# SFP.net
KiCad netlist of a schematic drawn in Altium Designer
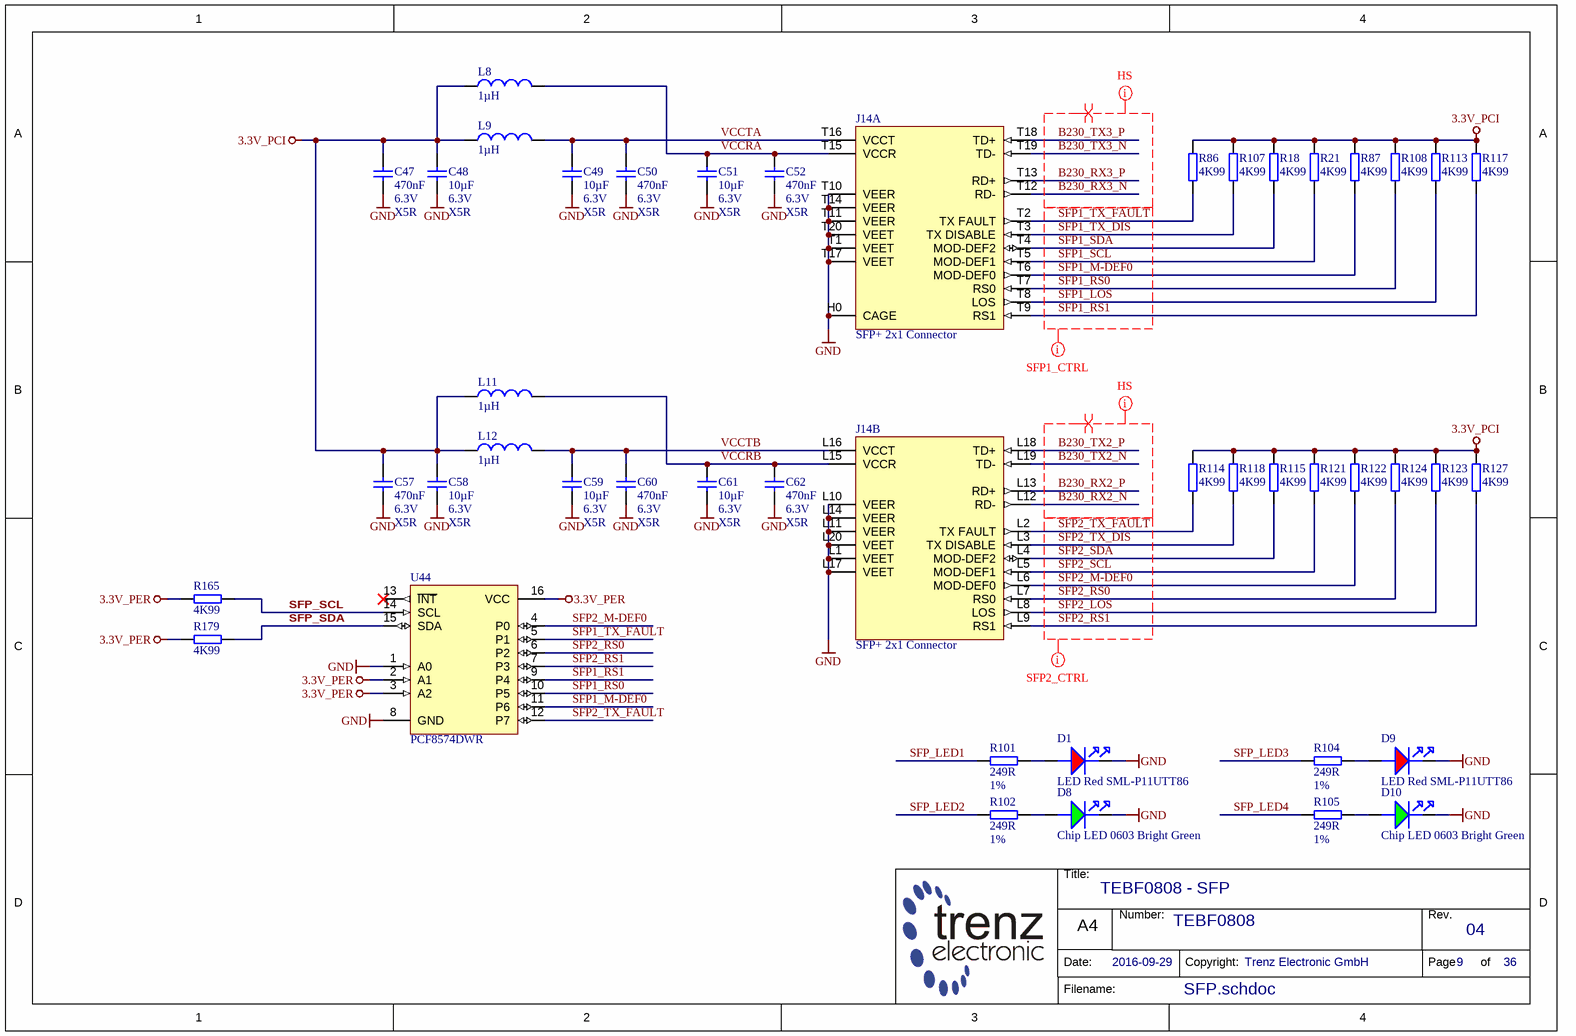
[diagram p0: SFP.schdoc]

(export (version "E")
  (design (tool "Eeschema 10.0.6"))
  (components
    (comp (ref "C47")
      (value "470nF")
      (footprint "CAPC1005X55N")
      (description "KON 470nF 6,3V X5R SMD")
      (fields (field (name "VOLTAGE") "6.3V") (field (name "TECHNOLOGY") "X5R"))
      (libsource (lib "TE") (part "CAP-NP"))
    )
    (comp (ref "C48")
      (value "10µF")
      (footprint "CAPC1608X90N")
      (description "KON 10µF 6,3V X5R SMD")
      (fields (field (name "VOLTAGE") "6.3V") (field (name "TECHNOLOGY") "X5R"))
      (libsource (lib "TE") (part "CAP-NP"))
    )
    (comp (ref "C49")
      (value "10µF")
      (footprint "CAPC1608X90N")
      (description "KON 10µF 6,3V X5R SMD")
      (fields (field (name "VOLTAGE") "6.3V") (field (name "TECHNOLOGY") "X5R"))
      (libsource (lib "TE") (part "CAP-NP"))
    )
    (comp (ref "C50")
      (value "470nF")
      (footprint "CAPC1005X55N")
      (description "KON 470nF 6,3V X5R SMD")
      (fields (field (name "VOLTAGE") "6.3V") (field (name "TECHNOLOGY") "X5R"))
      (libsource (lib "TE") (part "CAP-NP"))
    )
    (comp (ref "C51")
      (value "10µF")
      (footprint "CAPC1608X90N")
      (description "KON 10µF 6,3V X5R SMD")
      (fields (field (name "VOLTAGE") "6.3V") (field (name "TECHNOLOGY") "X5R"))
      (libsource (lib "TE") (part "CAP-NP"))
    )
    (comp (ref "C52")
      (value "470nF")
      (footprint "CAPC1005X55N")
      (description "KON 470nF 6,3V X5R SMD")
      (fields (field (name "VOLTAGE") "6.3V") (field (name "TECHNOLOGY") "X5R"))
      (libsource (lib "TE") (part "CAP-NP"))
    )
    (comp (ref "C57")
      (value "470nF")
      (footprint "CAPC1005X55N")
      (description "KON 470nF 6,3V X5R SMD")
      (fields (field (name "VOLTAGE") "6.3V") (field (name "TECHNOLOGY") "X5R"))
      (libsource (lib "TE") (part "CAP-NP"))
    )
    (comp (ref "C58")
      (value "10µF")
      (footprint "CAPC1608X90N")
      (description "KON 10µF 6,3V X5R SMD")
      (fields (field (name "VOLTAGE") "6.3V") (field (name "TECHNOLOGY") "X5R"))
      (libsource (lib "TE") (part "CAP-NP"))
    )
    (comp (ref "C59")
      (value "10µF")
      (footprint "CAPC1608X90N")
      (description "KON 10µF 6,3V X5R SMD")
      (fields (field (name "VOLTAGE") "6.3V") (field (name "TECHNOLOGY") "X5R"))
      (libsource (lib "TE") (part "CAP-NP"))
    )
    (comp (ref "C60")
      (value "470nF")
      (footprint "CAPC1005X55N")
      (description "KON 470nF 6,3V X5R SMD")
      (fields (field (name "VOLTAGE") "6.3V") (field (name "TECHNOLOGY") "X5R"))
      (libsource (lib "TE") (part "CAP-NP"))
    )
    (comp (ref "C61")
      (value "10µF")
      (footprint "CAPC1608X90N")
      (description "KON 10µF 6,3V X5R SMD")
      (fields (field (name "VOLTAGE") "6.3V") (field (name "TECHNOLOGY") "X5R"))
      (libsource (lib "TE") (part "CAP-NP"))
    )
    (comp (ref "C62")
      (value "470nF")
      (footprint "CAPC1005X55N")
      (description "KON 470nF 6,3V X5R SMD")
      (fields (field (name "VOLTAGE") "6.3V") (field (name "TECHNOLOGY") "X5R"))
      (libsource (lib "TE") (part "CAP-NP"))
    )
    (comp (ref "D1")
      (value "LED Red SML-P11UTT86")
      (footprint "LEDC1006X25N_RED")
      (description "LED Rot SML-P11UTT86 SMD")
      (libsource (lib "TE") (part "LED_ROT"))
    )
    (comp (ref "D8")
      (value "Chip LED 0603 Bright Green")
      (footprint "chipLED_0603_Green")
      (fields (field (name "VOLTAGE") "2.0"))
      (libsource (lib "TE") (part "LED_GRUEN"))
    )
    (comp (ref "D9")
      (value "LED Red SML-P11UTT86")
      (footprint "LEDC1006X25N_RED")
      (description "LED Rot SML-P11UTT86 SMD")
      (libsource (lib "TE") (part "LED_ROT"))
    )
    (comp (ref "D10")
      (value "Chip LED 0603 Bright Green")
      (footprint "chipLED_0603_Green")
      (fields (field (name "VOLTAGE") "2.0"))
      (libsource (lib "TE") (part "LED_GRUEN"))
    )
    (comp (ref "J14")
      (value "SFP+ 2x1 Connector")
      (footprint "1-2007492-5")
      (description "SFP+ 2x1 Connector  Sp Fing 4LP EMI Enhanced")
      (libsource (lib "TE") (part "1-2007492-5"))
    )
    (comp (ref "L8")
      (value "1µH")
      (footprint "INDC2520X100N")
      (description "IND SMD 1µH +-20% 0.055Ohm")
      (fields (field (name "VOLTAGE") "1.7A"))
      (libsource (lib "TE") (part "IND"))
    )
    (comp (ref "L9")
      (value "1µH")
      (footprint "INDC2520X100N")
      (description "IND SMD 1µH +-20% 0.055Ohm")
      (fields (field (name "VOLTAGE") "1.7A"))
      (libsource (lib "TE") (part "IND"))
    )
    (comp (ref "L11")
      (value "1µH")
      (footprint "INDC2520X100N")
      (description "IND SMD 1µH +-20% 0.055Ohm")
      (fields (field (name "VOLTAGE") "1.7A"))
      (libsource (lib "TE") (part "IND"))
    )
    (comp (ref "L12")
      (value "1µH")
      (footprint "INDC2520X100N")
      (description "IND SMD 1µH +-20% 0.055Ohm")
      (fields (field (name "VOLTAGE") "1.7A"))
      (libsource (lib "TE") (part "IND"))
    )
    (comp (ref "R18")
      (value "4K99")
      (footprint "RESC1005X40N")
      (description "WID SMD 4K99 1% 0,063W")
      (fields (field (name "TOLERANCE") "1%"))
      (libsource (lib "TE") (part "RES"))
    )
    (comp (ref "R21")
      (value "4K99")
      (footprint "RESC1005X40N")
      (description "WID SMD 4K99 1% 0,063W")
      (fields (field (name "TOLERANCE") "1%"))
      (libsource (lib "TE") (part "RES"))
    )
    (comp (ref "R86")
      (value "4K99")
      (footprint "RESC1005X40N")
      (description "WID SMD 4K99 1% 0,063W")
      (fields (field (name "TOLERANCE") "1%"))
      (libsource (lib "TE") (part "RES"))
    )
    (comp (ref "R87")
      (value "4K99")
      (footprint "RESC1005X40N")
      (description "WID SMD 4K99 1% 0,063W")
      (fields (field (name "TOLERANCE") "1%"))
      (libsource (lib "TE") (part "RES"))
    )
    (comp (ref "R101")
      (value "249R")
      (footprint "RESC1005X40N")
      (description "WID SMD 249R 1% 0,063W")
      (fields (field (name "TOLERANCE") "1%"))
      (libsource (lib "TE") (part "RES"))
    )
    (comp (ref "R102")
      (value "249R")
      (footprint "RESC1005X40N")
      (description "WID SMD 249R 1% 0,063W")
      (fields (field (name "TOLERANCE") "1%"))
      (libsource (lib "TE") (part "RES"))
    )
    (comp (ref "R104")
      (value "249R")
      (footprint "RESC1005X40N")
      (description "WID SMD 249R 1% 0,063W")
      (fields (field (name "TOLERANCE") "1%"))
      (libsource (lib "TE") (part "RES"))
    )
    (comp (ref "R105")
      (value "249R")
      (footprint "RESC1005X40N")
      (description "WID SMD 249R 1% 0,063W")
      (fields (field (name "TOLERANCE") "1%"))
      (libsource (lib "TE") (part "RES"))
    )
    (comp (ref "R107")
      (value "4K99")
      (footprint "RESC1005X40N")
      (description "WID SMD 4K99 1% 0,063W")
      (fields (field (name "TOLERANCE") "1%"))
      (libsource (lib "TE") (part "RES"))
    )
    (comp (ref "R108")
      (value "4K99")
      (footprint "RESC1005X40N")
      (description "WID SMD 4K99 1% 0,063W")
      (fields (field (name "TOLERANCE") "1%"))
      (libsource (lib "TE") (part "RES"))
    )
    (comp (ref "R113")
      (value "4K99")
      (footprint "RESC1005X40N")
      (description "WID SMD 4K99 1% 0,063W")
      (fields (field (name "TOLERANCE") "1%"))
      (libsource (lib "TE") (part "RES"))
    )
    (comp (ref "R114")
      (value "4K99")
      (footprint "RESC1005X40N")
      (description "WID SMD 4K99 1% 0,063W")
      (fields (field (name "TOLERANCE") "1%"))
      (libsource (lib "TE") (part "RES"))
    )
    (comp (ref "R115")
      (value "4K99")
      (footprint "RESC1005X40N")
      (description "WID SMD 4K99 1% 0,063W")
      (fields (field (name "TOLERANCE") "1%"))
      (libsource (lib "TE") (part "RES"))
    )
    (comp (ref "R117")
      (value "4K99")
      (footprint "RESC1005X40N")
      (description "WID SMD 4K99 1% 0,063W")
      (fields (field (name "TOLERANCE") "1%"))
      (libsource (lib "TE") (part "RES"))
    )
    (comp (ref "R118")
      (value "4K99")
      (footprint "RESC1005X40N")
      (description "WID SMD 4K99 1% 0,063W")
      (fields (field (name "TOLERANCE") "1%"))
      (libsource (lib "TE") (part "RES"))
    )
    (comp (ref "R121")
      (value "4K99")
      (footprint "RESC1005X40N")
      (description "WID SMD 4K99 1% 0,063W")
      (fields (field (name "TOLERANCE") "1%"))
      (libsource (lib "TE") (part "RES"))
    )
    (comp (ref "R122")
      (value "4K99")
      (footprint "RESC1005X40N")
      (description "WID SMD 4K99 1% 0,063W")
      (fields (field (name "TOLERANCE") "1%"))
      (libsource (lib "TE") (part "RES"))
    )
    (comp (ref "R123")
      (value "4K99")
      (footprint "RESC1005X40N")
      (description "WID SMD 4K99 1% 0,063W")
      (fields (field (name "TOLERANCE") "1%"))
      (libsource (lib "TE") (part "RES"))
    )
    (comp (ref "R124")
      (value "4K99")
      (footprint "RESC1005X40N")
      (description "WID SMD 4K99 1% 0,063W")
      (fields (field (name "TOLERANCE") "1%"))
      (libsource (lib "TE") (part "RES"))
    )
    (comp (ref "R127")
      (value "4K99")
      (footprint "RESC1005X40N")
      (description "WID SMD 4K99 1% 0,063W")
      (fields (field (name "TOLERANCE") "1%"))
      (libsource (lib "TE") (part "RES"))
    )
    (comp (ref "R165")
      (value "4K99")
      (footprint "RESC1005X40N")
      (description "WID SMD 4K99 1% 0,063W")
      (fields (field (name "TOLERANCE") "1%"))
      (libsource (lib "TE") (part "RES"))
    )
    (comp (ref "R179")
      (value "4K99")
      (footprint "RESC1005X40N")
      (description "WID SMD 4K99 1% 0,063W")
      (fields (field (name "TOLERANCE") "1%"))
      (libsource (lib "TE") (part "RES"))
    )
    (comp (ref "U44")
      (value "PCF8574DWR")
      (footprint "SOIC127P1030X265-16N")
      (libsource (lib "TE") (part "PCF8574DWR"))
    )
  )
  (nets
    (net (code "1") (name "/B230_RX2_N") (class "Default")
      (node (ref "J14") (pin "L12") (pinfunction "RD-_L12") (pintype "output"))
    )
    (net (code "2") (name "/B230_RX2_P") (class "Default")
      (node (ref "J14") (pin "L13") (pinfunction "RD+_L13") (pintype "output"))
    )
    (net (code "3") (name "/B230_RX3_N") (class "Default")
      (node (ref "J14") (pin "T12") (pinfunction "RD-_T12") (pintype "output"))
    )
    (net (code "4") (name "/B230_RX3_P") (class "Default")
      (node (ref "J14") (pin "T13") (pinfunction "RD+_T13") (pintype "output"))
    )
    (net (code "5") (name "/B230_TX2_N") (class "Default")
      (node (ref "J14") (pin "L19") (pinfunction "TD-_L19") (pintype "input"))
    )
    (net (code "6") (name "/B230_TX2_P") (class "Default")
      (node (ref "J14") (pin "L18") (pinfunction "TD+_L18") (pintype "input"))
    )
    (net (code "7") (name "/B230_TX3_N") (class "Default")
      (node (ref "J14") (pin "T19") (pinfunction "TD-_T19") (pintype "input"))
    )
    (net (code "8") (name "/B230_TX3_P") (class "Default")
      (node (ref "J14") (pin "T18") (pinfunction "TD+_T18") (pintype "input"))
    )
    (net (code "9") (name "/SFP1_LOS") (class "Default")
      (node (ref "J14") (pin "T8") (pinfunction "LOS_T8") (pintype "output"))
      (node (ref "R113") (pin "1") (pinfunction "1_1") (pintype "passive"))
    )
    (net (code "10") (name "/SFP1_M-DEF0") (class "Default")
      (node (ref "J14") (pin "T6") (pinfunction "MOD-DEF0_T6") (pintype "output"))
      (node (ref "R87") (pin "1") (pinfunction "1_1") (pintype "passive"))
      (node (ref "U44") (pin "11") (pinfunction "P6_11") (pintype "bidirectional"))
    )
    (net (code "11") (name "/SFP1_RS0") (class "Default")
      (node (ref "J14") (pin "T7") (pinfunction "RS0_T7") (pintype "input"))
      (node (ref "R108") (pin "1") (pinfunction "1_1") (pintype "passive"))
      (node (ref "U44") (pin "10") (pinfunction "P5_10") (pintype "bidirectional"))
    )
    (net (code "12") (name "/SFP1_RS1") (class "Default")
      (node (ref "J14") (pin "T9") (pinfunction "RS1_T9") (pintype "input"))
      (node (ref "R117") (pin "1") (pinfunction "1_1") (pintype "passive"))
      (node (ref "U44") (pin "9") (pinfunction "P4_9") (pintype "bidirectional"))
    )
    (net (code "13") (name "/SFP1_SCL") (class "Default")
      (node (ref "J14") (pin "T5") (pinfunction "MOD-DEF1_T5") (pintype "input"))
      (node (ref "R21") (pin "1") (pinfunction "1_1") (pintype "passive"))
    )
    (net (code "14") (name "/SFP1_SDA") (class "Default")
      (node (ref "J14") (pin "T4") (pinfunction "MOD-DEF2_T4") (pintype "bidirectional"))
      (node (ref "R18") (pin "1") (pinfunction "1_1") (pintype "passive"))
    )
    (net (code "15") (name "/SFP1_TX_DIS") (class "Default")
      (node (ref "J14") (pin "T3") (pinfunction "TX_DISABLE_T3") (pintype "input"))
      (node (ref "R107") (pin "1") (pinfunction "1_1") (pintype "passive"))
    )
    (net (code "16") (name "/SFP1_TX_FAULT") (class "Default")
      (node (ref "J14") (pin "T2") (pinfunction "TX_FAULT_T2") (pintype "output"))
      (node (ref "R86") (pin "1") (pinfunction "1_1") (pintype "passive"))
      (node (ref "U44") (pin "5") (pinfunction "P1_5") (pintype "bidirectional"))
    )
    (net (code "17") (name "/SFP2_LOS") (class "Default")
      (node (ref "J14") (pin "L8") (pinfunction "LOS_L8") (pintype "output"))
      (node (ref "R123") (pin "1") (pinfunction "1_1") (pintype "passive"))
    )
    (net (code "18") (name "/SFP2_M-DEF0") (class "Default")
      (node (ref "J14") (pin "L6") (pinfunction "MOD-DEF0_L6") (pintype "output"))
      (node (ref "R122") (pin "1") (pinfunction "1_1") (pintype "passive"))
      (node (ref "U44") (pin "4") (pinfunction "P0_4") (pintype "bidirectional"))
    )
    (net (code "19") (name "/SFP2_RS0") (class "Default")
      (node (ref "J14") (pin "L7") (pinfunction "RS0_L7") (pintype "input"))
      (node (ref "R124") (pin "1") (pinfunction "1_1") (pintype "passive"))
      (node (ref "U44") (pin "6") (pinfunction "P2_6") (pintype "bidirectional"))
    )
    (net (code "20") (name "/SFP2_RS1") (class "Default")
      (node (ref "J14") (pin "L9") (pinfunction "RS1_L9") (pintype "input"))
      (node (ref "R127") (pin "1") (pinfunction "1_1") (pintype "passive"))
      (node (ref "U44") (pin "7") (pinfunction "P3_7") (pintype "bidirectional"))
    )
    (net (code "21") (name "/SFP2_SCL") (class "Default")
      (node (ref "J14") (pin "L5") (pinfunction "MOD-DEF1_L5") (pintype "input"))
      (node (ref "R121") (pin "1") (pinfunction "1_1") (pintype "passive"))
    )
    (net (code "22") (name "/SFP2_SDA") (class "Default")
      (node (ref "J14") (pin "L4") (pinfunction "MOD-DEF2_L4") (pintype "bidirectional"))
      (node (ref "R115") (pin "1") (pinfunction "1_1") (pintype "passive"))
    )
    (net (code "23") (name "/SFP2_TX_DIS") (class "Default")
      (node (ref "J14") (pin "L3") (pinfunction "TX_DISABLE_L3") (pintype "input"))
      (node (ref "R118") (pin "1") (pinfunction "1_1") (pintype "passive"))
    )
    (net (code "24") (name "/SFP2_TX_FAULT") (class "Default")
      (node (ref "J14") (pin "L2") (pinfunction "TX_FAULT_L2") (pintype "output"))
      (node (ref "R114") (pin "1") (pinfunction "1_1") (pintype "passive"))
      (node (ref "U44") (pin "12") (pinfunction "P7_12") (pintype "bidirectional"))
    )
    (net (code "25") (name "/SFP_LED1") (class "Default")
      (node (ref "R101") (pin "1") (pinfunction "1_1") (pintype "passive"))
    )
    (net (code "26") (name "/SFP_LED2") (class "Default")
      (node (ref "R102") (pin "1") (pinfunction "1_1") (pintype "passive"))
    )
    (net (code "27") (name "/SFP_LED3") (class "Default")
      (node (ref "R104") (pin "1") (pinfunction "1_1") (pintype "passive"))
    )
    (net (code "28") (name "/SFP_LED4") (class "Default")
      (node (ref "R105") (pin "1") (pinfunction "1_1") (pintype "passive"))
    )
    (net (code "29") (name "/SFP_SCL") (class "Default")
      (node (ref "R165") (pin "2") (pinfunction "2_2") (pintype "passive"))
      (node (ref "U44") (pin "14") (pinfunction "SCL_14") (pintype "input"))
    )
    (net (code "30") (name "/SFP_SDA") (class "Default")
      (node (ref "R179") (pin "2") (pinfunction "2_2") (pintype "passive"))
      (node (ref "U44") (pin "15") (pinfunction "SDA_15") (pintype "bidirectional"))
    )
    (net (code "31") (name "/VCCRA") (class "Default")
      (node (ref "C51") (pin "1") (pinfunction "1_1") (pintype "passive"))
      (node (ref "C52") (pin "1") (pinfunction "1_1") (pintype "passive"))
      (node (ref "J14") (pin "T15") (pinfunction "VCCR_T15") (pintype "power_in"))
      (node (ref "L8") (pin "2") (pinfunction "2_2") (pintype "passive"))
    )
    (net (code "32") (name "/VCCRB") (class "Default")
      (node (ref "C61") (pin "1") (pinfunction "1_1") (pintype "passive"))
      (node (ref "C62") (pin "1") (pinfunction "1_1") (pintype "passive"))
      (node (ref "J14") (pin "L15") (pinfunction "VCCR_L15") (pintype "power_in"))
      (node (ref "L11") (pin "2") (pinfunction "2_2") (pintype "passive"))
    )
    (net (code "33") (name "/VCCTA") (class "Default")
      (node (ref "C49") (pin "1") (pinfunction "1_1") (pintype "passive"))
      (node (ref "C50") (pin "1") (pinfunction "1_1") (pintype "passive"))
      (node (ref "J14") (pin "T16") (pinfunction "VCCT_T16") (pintype "power_in"))
      (node (ref "L9") (pin "2") (pinfunction "2_2") (pintype "passive"))
    )
    (net (code "34") (name "/VCCTB") (class "Default")
      (node (ref "C59") (pin "1") (pinfunction "1_1") (pintype "passive"))
      (node (ref "C60") (pin "1") (pinfunction "1_1") (pintype "passive"))
      (node (ref "J14") (pin "L16") (pinfunction "VCCT_L16") (pintype "power_in"))
      (node (ref "L12") (pin "2") (pinfunction "2_2") (pintype "passive"))
    )
    (net (code "35") (name "3.3V_PCI") (class "Default")
      (node (ref "C47") (pin "1") (pinfunction "1_1") (pintype "passive"))
      (node (ref "C48") (pin "1") (pinfunction "1_1") (pintype "passive"))
      (node (ref "C57") (pin "1") (pinfunction "1_1") (pintype "passive"))
      (node (ref "C58") (pin "1") (pinfunction "1_1") (pintype "passive"))
      (node (ref "L11") (pin "1") (pinfunction "1_1") (pintype "passive"))
      (node (ref "L12") (pin "1") (pinfunction "1_1") (pintype "passive"))
      (node (ref "L8") (pin "1") (pinfunction "1_1") (pintype "passive"))
      (node (ref "L9") (pin "1") (pinfunction "1_1") (pintype "passive"))
      (node (ref "R107") (pin "2") (pinfunction "2_2") (pintype "passive"))
      (node (ref "R108") (pin "2") (pinfunction "2_2") (pintype "passive"))
      (node (ref "R113") (pin "2") (pinfunction "2_2") (pintype "passive"))
      (node (ref "R114") (pin "2") (pinfunction "2_2") (pintype "passive"))
      (node (ref "R115") (pin "2") (pinfunction "2_2") (pintype "passive"))
      (node (ref "R117") (pin "2") (pinfunction "2_2") (pintype "passive"))
      (node (ref "R118") (pin "2") (pinfunction "2_2") (pintype "passive"))
      (node (ref "R121") (pin "2") (pinfunction "2_2") (pintype "passive"))
      (node (ref "R122") (pin "2") (pinfunction "2_2") (pintype "passive"))
      (node (ref "R123") (pin "2") (pinfunction "2_2") (pintype "passive"))
      (node (ref "R124") (pin "2") (pinfunction "2_2") (pintype "passive"))
      (node (ref "R127") (pin "2") (pinfunction "2_2") (pintype "passive"))
      (node (ref "R18") (pin "2") (pinfunction "2_2") (pintype "passive"))
      (node (ref "R21") (pin "2") (pinfunction "2_2") (pintype "passive"))
      (node (ref "R86") (pin "2") (pinfunction "2_2") (pintype "passive"))
      (node (ref "R87") (pin "2") (pinfunction "2_2") (pintype "passive"))
    )
    (net (code "36") (name "3.3V_PER") (class "Default")
      (node (ref "R165") (pin "1") (pinfunction "1_1") (pintype "passive"))
      (node (ref "R179") (pin "1") (pinfunction "1_1") (pintype "passive"))
      (node (ref "U44") (pin "16") (pinfunction "VCC_16") (pintype "power_in"))
      (node (ref "U44") (pin "2") (pinfunction "A1_2") (pintype "input"))
      (node (ref "U44") (pin "3") (pinfunction "A2_3") (pintype "input"))
    )
    (net (code "37") (name "GND") (class "Default")
      (node (ref "C47") (pin "2") (pinfunction "2_2") (pintype "passive"))
      (node (ref "C48") (pin "2") (pinfunction "2_2") (pintype "passive"))
      (node (ref "C49") (pin "2") (pinfunction "2_2") (pintype "passive"))
      (node (ref "C50") (pin "2") (pinfunction "2_2") (pintype "passive"))
      (node (ref "C51") (pin "2") (pinfunction "2_2") (pintype "passive"))
      (node (ref "C52") (pin "2") (pinfunction "2_2") (pintype "passive"))
      (node (ref "C57") (pin "2") (pinfunction "2_2") (pintype "passive"))
      (node (ref "C58") (pin "2") (pinfunction "2_2") (pintype "passive"))
      (node (ref "C59") (pin "2") (pinfunction "2_2") (pintype "passive"))
      (node (ref "C60") (pin "2") (pinfunction "2_2") (pintype "passive"))
      (node (ref "C61") (pin "2") (pinfunction "2_2") (pintype "passive"))
      (node (ref "C62") (pin "2") (pinfunction "2_2") (pintype "passive"))
      (node (ref "D1") (pin "K") (pinfunction "K_K") (pintype "passive"))
      (node (ref "D10") (pin "K") (pinfunction "K_K") (pintype "passive"))
      (node (ref "D8") (pin "K") (pinfunction "K_K") (pintype "passive"))
      (node (ref "D9") (pin "K") (pinfunction "K_K") (pintype "passive"))
      (node (ref "J14") (pin "H0") (pinfunction "CAGE_H0") (pintype "power_in"))
      (node (ref "J14") (pin "L1") (pinfunction "VEET_L1") (pintype "power_in"))
      (node (ref "J14") (pin "L10") (pinfunction "VEER_L10") (pintype "power_in"))
      (node (ref "J14") (pin "L11") (pinfunction "VEER_L11") (pintype "power_in"))
      (node (ref "J14") (pin "L14") (pinfunction "VEER_L14") (pintype "power_in"))
      (node (ref "J14") (pin "L17") (pinfunction "VEET_L17") (pintype "power_in"))
      (node (ref "J14") (pin "L20") (pinfunction "VEET_L20") (pintype "power_in"))
      (node (ref "J14") (pin "T1") (pinfunction "VEET_T1") (pintype "power_in"))
      (node (ref "J14") (pin "T10") (pinfunction "VEER_T10") (pintype "power_in"))
      (node (ref "J14") (pin "T11") (pinfunction "VEER_T11") (pintype "power_in"))
      (node (ref "J14") (pin "T14") (pinfunction "VEER_T14") (pintype "power_in"))
      (node (ref "J14") (pin "T17") (pinfunction "VEET_T17") (pintype "power_in"))
      (node (ref "J14") (pin "T20") (pinfunction "VEET_T20") (pintype "power_in"))
      (node (ref "U44") (pin "1") (pinfunction "A0_1") (pintype "input"))
      (node (ref "U44") (pin "8") (pinfunction "GND_8") (pintype "power_in"))
    )
    (net (code "38") (name "Net-(D1-PadA)") (class "Default")
      (node (ref "D1") (pin "A") (pinfunction "A_A") (pintype "passive"))
      (node (ref "R101") (pin "2") (pinfunction "2_2") (pintype "passive"))
    )
    (net (code "39") (name "Net-(D8-PadA)") (class "Default")
      (node (ref "D8") (pin "A") (pinfunction "A_A") (pintype "passive"))
      (node (ref "R102") (pin "2") (pinfunction "2_2") (pintype "passive"))
    )
    (net (code "40") (name "Net-(D9-PadA)") (class "Default")
      (node (ref "D9") (pin "A") (pinfunction "A_A") (pintype "passive"))
      (node (ref "R104") (pin "2") (pinfunction "2_2") (pintype "passive"))
    )
    (net (code "41") (name "Net-(D10-PadA)") (class "Default")
      (node (ref "D10") (pin "A") (pinfunction "A_A") (pintype "passive"))
      (node (ref "R105") (pin "2") (pinfunction "2_2") (pintype "passive"))
    )
    (net (code "42") (name "unconnected-(U44-~{INT}-Pad13)") (class "Default")
      (node (ref "U44") (pin "13") (pinfunction "~{INT}_13") (pintype "output+no_connect"))
    )
  )
)
